# OpenRobot.net
KiCad netlist of a schematic drawn in EAGLE
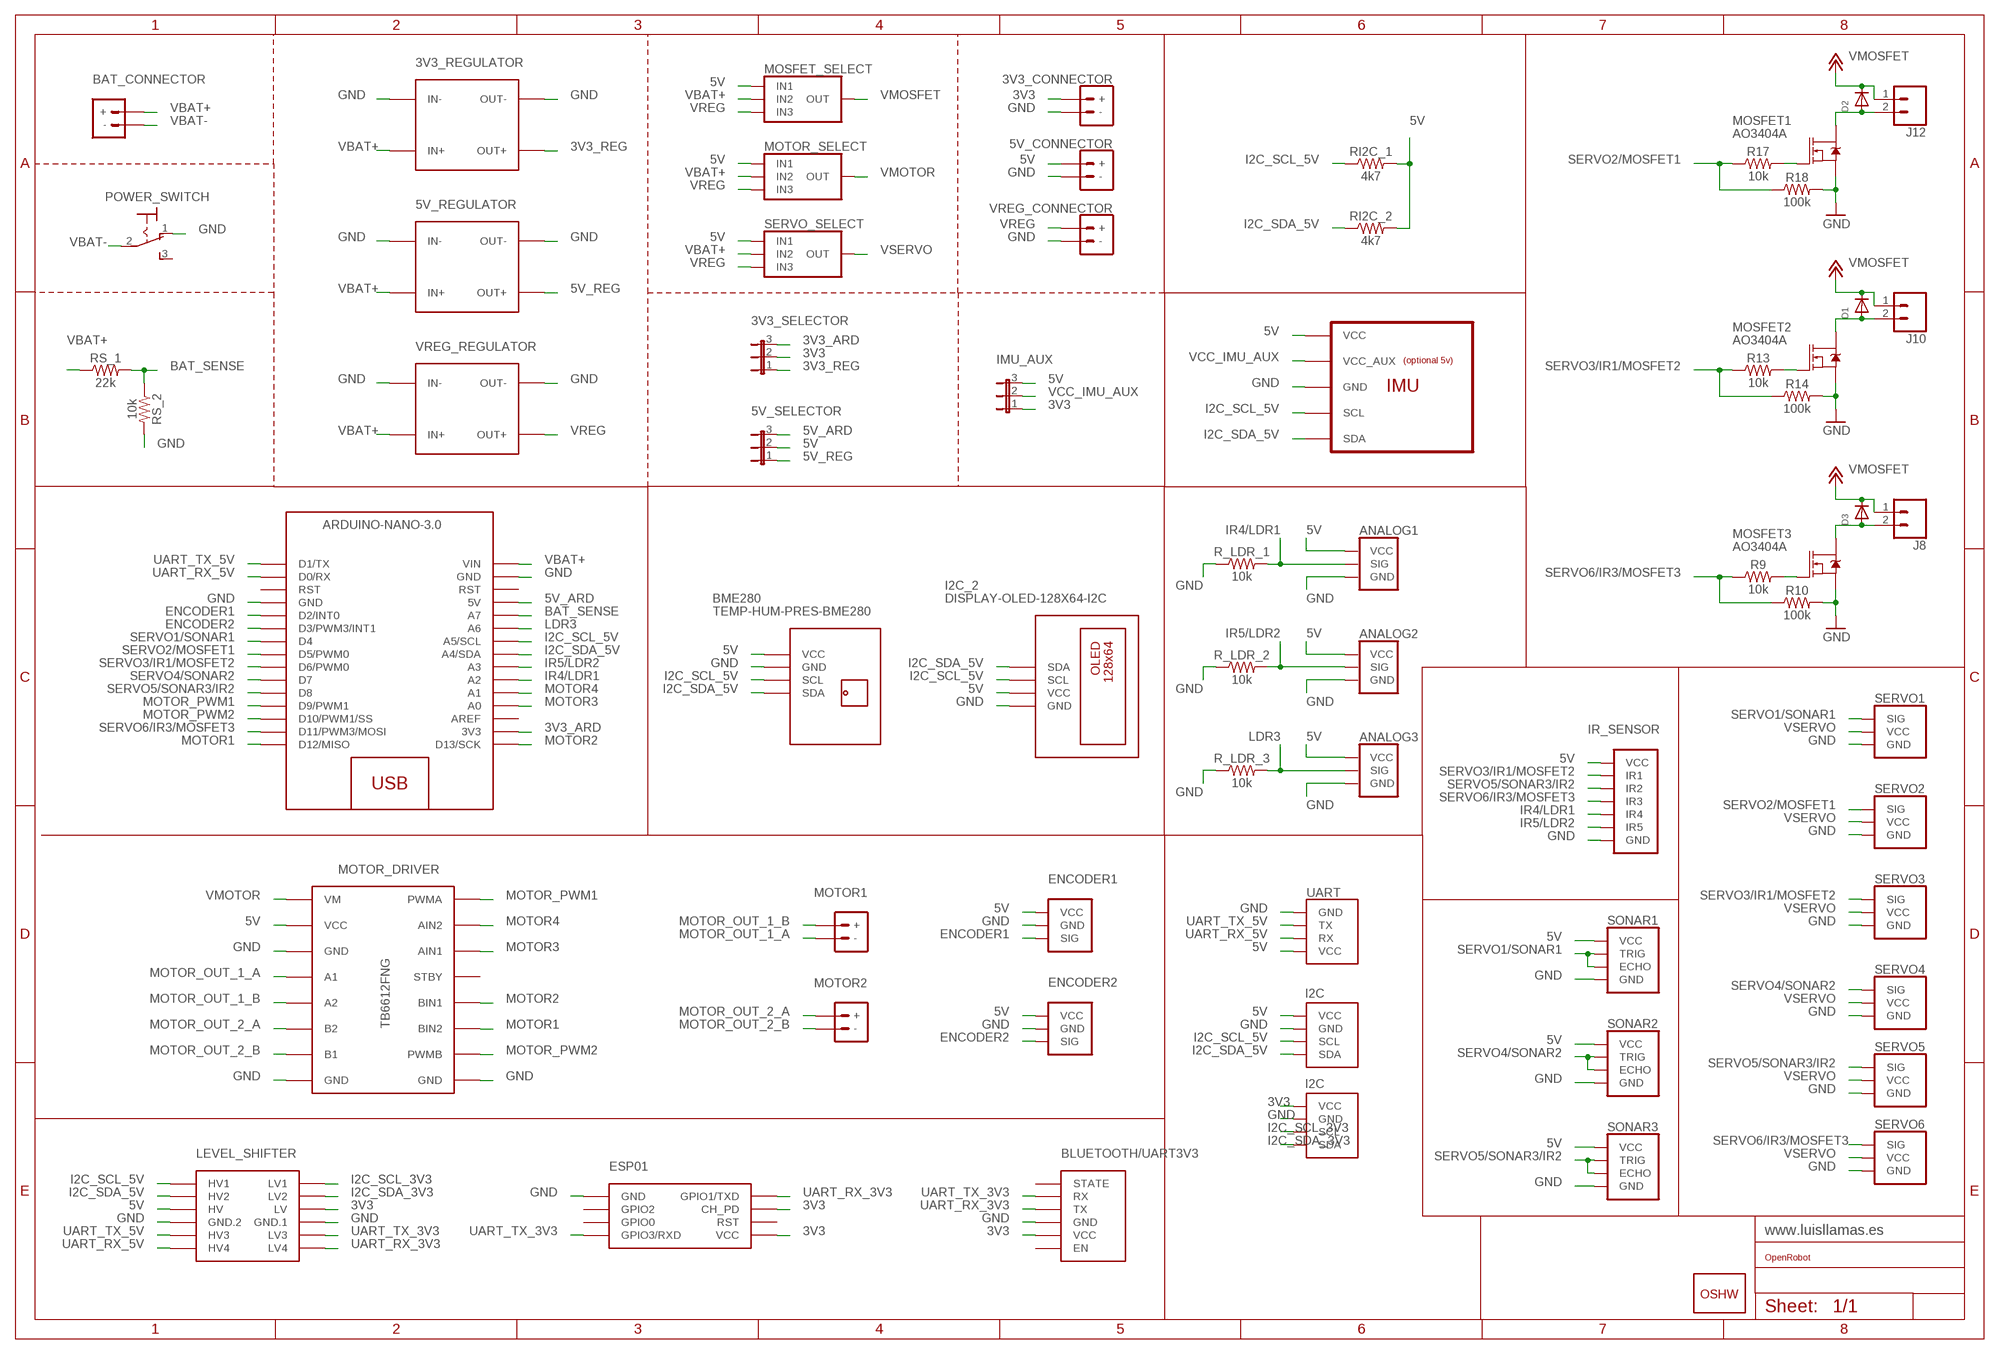
[diagram p0: schematic, sheet 1]

(export (version "E")
  (design (tool "Eeschema 10.0.6"))
  (components
    (comp (ref "3V3_CONNECTOR")
      (value "MOTOR-TERMINAL2.54MM_SCREWTERM")
      (footprint "eagle-import:1X02_2.54_SCREWTERM")
      (libsource (lib "eagle-import") (part "MOTOR-TERMINAL2.54MM_SCREWTERM"))
    )
    (comp (ref "3V3_REGULATOR")
      (value "MINI-DC-STEP-DOWN-MP2307")
      (footprint "eagle-import:MINI-DC-STEP-DOWN-MP2307")
      (libsource (lib "eagle-import") (part "MINI-DC-STEP-DOWN-MP2307"))
    )
    (comp (ref "3V3_SELECTOR")
      (value "1")
      (footprint "eagle-import:JP2")
      (libsource (lib "eagle-import") (part "JP2E"))
    )
    (comp (ref "5V_CONNECTOR")
      (value "MOTOR-TERMINAL2.54MM_SCREWTERM")
      (footprint "eagle-import:1X02_2.54_SCREWTERM")
      (libsource (lib "eagle-import") (part "MOTOR-TERMINAL2.54MM_SCREWTERM"))
    )
    (comp (ref "5V_REGULATOR")
      (value "MINI-DC-STEP-DOWN-MP2307")
      (footprint "eagle-import:MINI-DC-STEP-DOWN-MP2307")
      (libsource (lib "eagle-import") (part "MINI-DC-STEP-DOWN-MP2307"))
    )
    (comp (ref "5V_SELECTOR")
      (value "1")
      (footprint "eagle-import:JP2")
      (libsource (lib "eagle-import") (part "JP2E"))
    )
    (comp (ref "ANALOG1")
      (value "LDR/OCT")
      (footprint "eagle-import:LDR")
      (libsource (lib "eagle-import") (part "LDR/OCT"))
    )
    (comp (ref "ANALOG2")
      (value "LDR/OCT")
      (footprint "eagle-import:LDR")
      (libsource (lib "eagle-import") (part "LDR/OCT"))
    )
    (comp (ref "ANALOG3")
      (value "LDR/OCT")
      (footprint "eagle-import:LDR")
      (libsource (lib "eagle-import") (part "LDR/OCT"))
    )
    (comp (ref "ARDUINO_NANO1")
      (value "ARDUINO-NANO-3.0")
      (footprint "eagle-import:ARDUINO-NANO-3.0")
      (libsource (lib "eagle-import") (part "ARDUINO-NANO-3.0"))
    )
    (comp (ref "BAT_CONNECTOR")
      (value "POWER-TERMINAL5MM")
      (footprint "eagle-import:SCREWTERMINAL-5MM-2")
      (libsource (lib "eagle-import") (part "POWER-TERMINAL5MM"))
    )
    (comp (ref "BLUETOOTH/UART3V3")
      (value "BLUETOOTH-HC-05")
      (footprint "eagle-import:BLUETOOTH-HC-05")
      (libsource (lib "eagle-import") (part "BLUETOOTH-HC-05"))
    )
    (comp (ref "BME280")
      (value "TEMP-HUM-PRES-BME280")
      (footprint "eagle-import:TEMP-HUM-PRES-BME280")
      (libsource (lib "eagle-import") (part "TEMP-HUM-PRES-BME280"))
    )
    (comp (ref "D1")
      (value "DIODESOD-123")
      (footprint "eagle-import:SOD-123")
      (libsource (lib "eagle-import") (part "DIODESOD-123"))
    )
    (comp (ref "D2")
      (value "DIODESOD-123")
      (footprint "eagle-import:SOD-123")
      (libsource (lib "eagle-import") (part "DIODESOD-123"))
    )
    (comp (ref "D3")
      (value "DIODESOD-123")
      (footprint "eagle-import:SOD-123")
      (libsource (lib "eagle-import") (part "DIODESOD-123"))
    )
    (comp (ref "ENCODER1")
      (value "ENCODER/OCT")
      (footprint "eagle-import:ENCODER")
      (libsource (lib "eagle-import") (part "ENCODER/OCT"))
    )
    (comp (ref "ENCODER2")
      (value "ENCODER/OCT")
      (footprint "eagle-import:ENCODER")
      (libsource (lib "eagle-import") (part "ENCODER/OCT"))
    )
    (comp (ref "GOLD_ORB_SM1")
      (value "OSHWLOGO_GOLD_ORB_MED")
      (footprint "eagle-import:OSHW1")
      (libsource (lib "eagle-import") (part "OSHWLOGO_GOLD_ORB_MED"))
    )
    (comp (ref "I2C_1")
      (value "I2C")
      (footprint "eagle-import:I2C_VCC_GND_SCL_SDA")
      (libsource (lib "eagle-import") (part "GENERIC_I2CVCC_GND_SCL_SDA"))
    )
    (comp (ref "I2C_2")
      (value "DISPLAY-OLED-128X64-I2C")
      (footprint "eagle-import:DISPLAY-OLED-128X64-I2C")
      (libsource (lib "eagle-import") (part "DISPLAY-OLED-128X64-I2C"))
    )
    (comp (ref "I2C_3")
      (value "I2C")
      (footprint "eagle-import:I2C_VCC_GND_SCL_SDA")
      (libsource (lib "eagle-import") (part "GENERIC_I2CVCC_GND_SCL_SDA"))
    )
    (comp (ref "IMU_AUX")
      (value "1")
      (footprint "eagle-import:JP2")
      (libsource (lib "eagle-import") (part "JP2E"))
    )
    (comp (ref "IR_SENSOR")
      (value "IR-5/OCT")
      (footprint "eagle-import:IR-5")
      (libsource (lib "eagle-import") (part "IR-5/OCT"))
    )
    (comp (ref "J8")
      (value "CONN_02LOCK_LONGPADS")
      (footprint "eagle-import:1X02_LOCK_LONGPADS")
      (libsource (lib "eagle-import") (part "CONN_02LOCK_LONGPADS"))
    )
    (comp (ref "J10")
      (value "CONN_02LOCK_LONGPADS")
      (footprint "eagle-import:1X02_LOCK_LONGPADS")
      (libsource (lib "eagle-import") (part "CONN_02LOCK_LONGPADS"))
    )
    (comp (ref "J12")
      (value "CONN_02LOCK_LONGPADS")
      (footprint "eagle-import:1X02_LOCK_LONGPADS")
      (libsource (lib "eagle-import") (part "CONN_02LOCK_LONGPADS"))
    )
    (comp (ref "LEVEL_SHIFTER")
      (value "LEVEL-SHIFTER-4CH")
      (footprint "eagle-import:LEVEL-SHIFTER-4CH")
      (libsource (lib "eagle-import") (part "LEVEL-SHIFTER-4CH"))
    )
    (comp (ref "MOSFET1")
      (value "AO3404A")
      (footprint "eagle-import:SOT23-3")
      (libsource (lib "eagle-import") (part "MOSFET-NCH-AO3404A"))
    )
    (comp (ref "MOSFET2")
      (value "AO3404A")
      (footprint "eagle-import:SOT23-3")
      (libsource (lib "eagle-import") (part "MOSFET-NCH-AO3404A"))
    )
    (comp (ref "MOSFET3")
      (value "AO3404A")
      (footprint "eagle-import:SOT23-3")
      (libsource (lib "eagle-import") (part "MOSFET-NCH-AO3404A"))
    )
    (comp (ref "MOSFET_SELECT")
      (value "JUMPER_3-1")
      (footprint "eagle-import:JUMPER_3-1")
      (libsource (lib "eagle-import") (part "JUMPER_3-1"))
    )
    (comp (ref "MOTOR1")
      (value "MOTOR-TERMINAL5MM")
      (footprint "eagle-import:SCREWTERMINAL-5MM-2")
      (libsource (lib "eagle-import") (part "MOTOR-TERMINAL5MM"))
    )
    (comp (ref "MOTOR2")
      (value "MOTOR-TERMINAL5MM")
      (footprint "eagle-import:SCREWTERMINAL-5MM-2")
      (libsource (lib "eagle-import") (part "MOTOR-TERMINAL5MM"))
    )
    (comp (ref "MOTOR_DRIVER")
      (value "TB6612FNG")
      (footprint "eagle-import:TB6612FNG")
      (libsource (lib "eagle-import") (part "TB6612FNG"))
    )
    (comp (ref "MOTOR_SELECT")
      (value "JUMPER_3-1")
      (footprint "eagle-import:JUMPER_3-1")
      (libsource (lib "eagle-import") (part "JUMPER_3-1"))
    )
    (comp (ref "POWER_SWITCH")
      (value "LEVER-POWER-SWITCH")
      (footprint "eagle-import:M9040P")
      (libsource (lib "eagle-import") (part "LEVER-POWER-SWITCH"))
    )
    (comp (ref "R9")
      (value "10k")
      (footprint "eagle-import:1206")
      (libsource (lib "eagle-import") (part "RESISTOR1206"))
    )
    (comp (ref "R10")
      (value "100k")
      (footprint "eagle-import:1206")
      (libsource (lib "eagle-import") (part "RESISTOR1206"))
    )
    (comp (ref "R13")
      (value "10k")
      (footprint "eagle-import:1206")
      (libsource (lib "eagle-import") (part "RESISTOR1206"))
    )
    (comp (ref "R14")
      (value "100k")
      (footprint "eagle-import:1206")
      (libsource (lib "eagle-import") (part "RESISTOR1206"))
    )
    (comp (ref "R17")
      (value "10k")
      (footprint "eagle-import:1206")
      (libsource (lib "eagle-import") (part "RESISTOR1206"))
    )
    (comp (ref "R18")
      (value "100k")
      (footprint "eagle-import:1206")
      (libsource (lib "eagle-import") (part "RESISTOR1206"))
    )
    (comp (ref "RI2C_1")
      (value "4k7")
      (footprint "eagle-import:1206")
      (libsource (lib "eagle-import") (part "RESISTOR1206"))
    )
    (comp (ref "RI2C_2")
      (value "4k7")
      (footprint "eagle-import:1206")
      (libsource (lib "eagle-import") (part "RESISTOR1206"))
    )
    (comp (ref "RS_1")
      (value "22k")
      (footprint "eagle-import:1206")
      (libsource (lib "eagle-import") (part "RESISTOR1206"))
    )
    (comp (ref "RS_2")
      (value "10k")
      (footprint "eagle-import:1206")
      (libsource (lib "eagle-import") (part "RESISTOR1206"))
    )
    (comp (ref "R_LDR_1")
      (value "10k")
      (footprint "eagle-import:1206")
      (libsource (lib "eagle-import") (part "RESISTOR1206"))
    )
    (comp (ref "R_LDR_2")
      (value "10k")
      (footprint "eagle-import:1206")
      (libsource (lib "eagle-import") (part "RESISTOR1206"))
    )
    (comp (ref "R_LDR_3")
      (value "10k")
      (footprint "eagle-import:1206")
      (libsource (lib "eagle-import") (part "RESISTOR1206"))
    )
    (comp (ref "SERVO1")
      (value "SERVOSERVO")
      (footprint "eagle-import:SERVO")
      (libsource (lib "eagle-import") (part "SERVOSERVO"))
    )
    (comp (ref "SERVO2")
      (value "SERVOSERVO")
      (footprint "eagle-import:SERVO")
      (libsource (lib "eagle-import") (part "SERVOSERVO"))
    )
    (comp (ref "SERVO3")
      (value "SERVOSERVO")
      (footprint "eagle-import:SERVO")
      (libsource (lib "eagle-import") (part "SERVOSERVO"))
    )
    (comp (ref "SERVO4")
      (value "SERVOSERVO")
      (footprint "eagle-import:SERVO")
      (libsource (lib "eagle-import") (part "SERVOSERVO"))
    )
    (comp (ref "SERVO5")
      (value "SERVOSERVO")
      (footprint "eagle-import:SERVO")
      (libsource (lib "eagle-import") (part "SERVOSERVO"))
    )
    (comp (ref "SERVO6")
      (value "SERVOSERVO")
      (footprint "eagle-import:SERVO")
      (libsource (lib "eagle-import") (part "SERVOSERVO"))
    )
    (comp (ref "SERVO_SELECT")
      (value "JUMPER_3-1")
      (footprint "eagle-import:JUMPER_3-1")
      (libsource (lib "eagle-import") (part "JUMPER_3-1"))
    )
    (comp (ref "SONAR1")
      (value "ULTRASONIC/OCT")
      (footprint "eagle-import:ULTRASONIC")
      (libsource (lib "eagle-import") (part "ULTRASONIC/OCT"))
    )
    (comp (ref "SONAR2")
      (value "ULTRASONIC/OCT")
      (footprint "eagle-import:ULTRASONIC")
      (libsource (lib "eagle-import") (part "ULTRASONIC/OCT"))
    )
    (comp (ref "SONAR3")
      (value "ULTRASONIC/OCT")
      (footprint "eagle-import:ULTRASONIC")
      (libsource (lib "eagle-import") (part "ULTRASONIC/OCT"))
    )
    (comp (ref "U$1")
      (value "ESP01")
      (footprint "eagle-import:ESP01")
      (libsource (lib "eagle-import") (part "ESP01"))
    )
    (comp (ref "U1")
      (value "IMU_6/9/10DOFMPU6050")
      (footprint "eagle-import:IMU_6_9_10DOF")
      (libsource (lib "eagle-import") (part "IMU_6/9/10DOFMPU6050"))
    )
    (comp (ref "UART")
      (value "UART")
      (footprint "eagle-import:GENERIC_UART")
      (libsource (lib "eagle-import") (part "GENERIC_UARTGND_TX_RX_VCC"))
    )
    (comp (ref "VREG_CONNECTOR")
      (value "MOTOR-TERMINAL2.54MM_SCREWTERM")
      (footprint "eagle-import:1X02_2.54_SCREWTERM")
      (libsource (lib "eagle-import") (part "MOTOR-TERMINAL2.54MM_SCREWTERM"))
    )
    (comp (ref "VREG_REGULATOR")
      (value "MINI-DC-STEP-DOWN-MP2307")
      (footprint "eagle-import:MINI-DC-STEP-DOWN-MP2307")
      (libsource (lib "eagle-import") (part "MINI-DC-STEP-DOWN-MP2307"))
    )
  )
  (nets
    (net (code "1") (name "+12V") (class "Default")
      (node (ref "D1") (pin "C") (pinfunction "C_C") (pintype "passive"))
      (node (ref "D2") (pin "C") (pinfunction "C_C") (pintype "passive"))
      (node (ref "D3") (pin "C") (pinfunction "C_C") (pintype "passive"))
      (node (ref "J10") (pin "1") (pinfunction "1_1") (pintype "passive"))
      (node (ref "J12") (pin "1") (pinfunction "1_1") (pintype "passive"))
      (node (ref "J8") (pin "1") (pinfunction "1_1") (pintype "passive"))
      (node (ref "MOSFET_SELECT") (pin "OUT") (pinfunction "OUT_OUT") (pintype "passive"))
    )
    (net (code "2") (name "/3V3") (class "Default")
      (node (ref "3V3_CONNECTOR") (pin "+") (pinfunction "+_+") (pintype "passive"))
      (node (ref "3V3_SELECTOR") (pin "2") (pinfunction "2_2") (pintype "passive"))
      (node (ref "BLUETOOTH/UART3V3") (pin "VCC") (pinfunction "VCC_VCC") (pintype "power_in"))
      (node (ref "I2C_3") (pin "VCC") (pinfunction "VCC_VCC") (pintype "power_in"))
      (node (ref "IMU_AUX") (pin "1") (pinfunction "1_1") (pintype "passive"))
      (node (ref "LEVEL_SHIFTER") (pin "J1.3") (pinfunction "LV_J1.3") (pintype "power_in"))
      (node (ref "U$1") (pin "CH_PD") (pinfunction "CH_PD_CH_PD") (pintype "bidirectional"))
      (node (ref "U$1") (pin "VCC") (pinfunction "VCC_VCC") (pintype "power_in"))
    )
    (net (code "3") (name "/3V3_ARD") (class "Default")
      (node (ref "3V3_SELECTOR") (pin "3") (pinfunction "3_3") (pintype "passive"))
      (node (ref "ARDUINO_NANO1") (pin "3V3") (pinfunction "3V3_3V3") (pintype "power_in"))
    )
    (net (code "4") (name "/3V3_REG") (class "Default")
      (node (ref "3V3_REGULATOR") (pin "OUT+") (pinfunction "OUT+_OUT+") (pintype "bidirectional"))
      (node (ref "3V3_REGULATOR") (pin "OUT2.+") (pinfunction "OUT+_OUT2.+") (pintype "bidirectional"))
      (node (ref "3V3_SELECTOR") (pin "1") (pinfunction "1_1") (pintype "passive"))
    )
    (net (code "5") (name "/5V") (class "Default")
      (node (ref "5V_CONNECTOR") (pin "+") (pinfunction "+_+") (pintype "passive"))
      (node (ref "5V_SELECTOR") (pin "2") (pinfunction "2_2") (pintype "passive"))
      (node (ref "ANALOG1") (pin "VCC") (pinfunction "VCC_VCC") (pintype "power_in"))
      (node (ref "ANALOG2") (pin "VCC") (pinfunction "VCC_VCC") (pintype "power_in"))
      (node (ref "ANALOG3") (pin "VCC") (pinfunction "VCC_VCC") (pintype "power_in"))
      (node (ref "BME280") (pin "VCC") (pinfunction "VCC_VCC") (pintype "power_in"))
      (node (ref "ENCODER1") (pin "VCC") (pinfunction "VCC_VCC") (pintype "power_in"))
      (node (ref "ENCODER2") (pin "VCC") (pinfunction "VCC_VCC") (pintype "power_in"))
      (node (ref "I2C_1") (pin "VCC") (pinfunction "VCC_VCC") (pintype "power_in"))
      (node (ref "I2C_2") (pin "VCC") (pinfunction "VCC_VCC") (pintype "power_in"))
      (node (ref "IMU_AUX") (pin "3") (pinfunction "3_3") (pintype "passive"))
      (node (ref "IR_SENSOR") (pin "VCC") (pinfunction "VCC_VCC") (pintype "power_in"))
      (node (ref "LEVEL_SHIFTER") (pin "J2.3") (pinfunction "HV_J2.3") (pintype "power_in"))
      (node (ref "MOSFET_SELECT") (pin "IN1") (pinfunction "IN1_IN1") (pintype "passive"))
      (node (ref "MOTOR_DRIVER") (pin "VCC") (pinfunction "VCC_VCC") (pintype "power_in"))
      (node (ref "MOTOR_SELECT") (pin "IN1") (pinfunction "IN1_IN1") (pintype "passive"))
      (node (ref "RI2C_1") (pin "2") (pinfunction "2_2") (pintype "passive"))
      (node (ref "RI2C_2") (pin "2") (pinfunction "2_2") (pintype "passive"))
      (node (ref "SERVO_SELECT") (pin "IN1") (pinfunction "IN1_IN1") (pintype "passive"))
      (node (ref "SONAR1") (pin "VCC") (pinfunction "VCC_VCC") (pintype "power_in"))
      (node (ref "SONAR2") (pin "VCC") (pinfunction "VCC_VCC") (pintype "power_in"))
      (node (ref "SONAR3") (pin "VCC") (pinfunction "VCC_VCC") (pintype "power_in"))
      (node (ref "U1") (pin "VCC") (pinfunction "VCC_VCC") (pintype "power_in"))
      (node (ref "UART") (pin "VCC") (pinfunction "VCC_VCC") (pintype "bidirectional"))
    )
    (net (code "6") (name "/5V_ARD") (class "Default")
      (node (ref "5V_SELECTOR") (pin "3") (pinfunction "3_3") (pintype "passive"))
      (node (ref "ARDUINO_NANO1") (pin "5V") (pinfunction "5V_5V") (pintype "bidirectional"))
    )
    (net (code "7") (name "/5V_REG") (class "Default")
      (node (ref "5V_REGULATOR") (pin "OUT+") (pinfunction "OUT+_OUT+") (pintype "bidirectional"))
      (node (ref "5V_REGULATOR") (pin "OUT2.+") (pinfunction "OUT+_OUT2.+") (pintype "bidirectional"))
      (node (ref "5V_SELECTOR") (pin "1") (pinfunction "1_1") (pintype "passive"))
    )
    (net (code "8") (name "/BAT_SENSE") (class "Default")
      (node (ref "ARDUINO_NANO1") (pin "A7") (pinfunction "A7_A7") (pintype "bidirectional"))
      (node (ref "RS_1") (pin "2") (pinfunction "2_2") (pintype "passive"))
      (node (ref "RS_2") (pin "1") (pinfunction "1_1") (pintype "passive"))
    )
    (net (code "9") (name "/ENCODER1") (class "Default")
      (node (ref "ARDUINO_NANO1") (pin "D2") (pinfunction "D2/INT0_D2") (pintype "bidirectional"))
      (node (ref "ENCODER1") (pin "SIG") (pinfunction "SIG_SIG") (pintype "bidirectional"))
    )
    (net (code "10") (name "/ENCODER2") (class "Default")
      (node (ref "ARDUINO_NANO1") (pin "D3") (pinfunction "D3/PWM3/INT1_D3") (pintype "bidirectional"))
      (node (ref "ENCODER2") (pin "SIG") (pinfunction "SIG_SIG") (pintype "bidirectional"))
    )
    (net (code "11") (name "/I2C_SCL_3V3") (class "Default")
      (node (ref "I2C_3") (pin "SCL") (pinfunction "SCL_SCL") (pintype "bidirectional"))
      (node (ref "LEVEL_SHIFTER") (pin "J1.1") (pinfunction "LV1_J1.1") (pintype "bidirectional"))
    )
    (net (code "12") (name "/I2C_SCL_5V") (class "Default")
      (node (ref "ARDUINO_NANO1") (pin "A5") (pinfunction "A5/SCL_A5") (pintype "bidirectional"))
      (node (ref "BME280") (pin "SCL") (pinfunction "SCL_SCL") (pintype "bidirectional"))
      (node (ref "I2C_1") (pin "SCL") (pinfunction "SCL_SCL") (pintype "bidirectional"))
      (node (ref "I2C_2") (pin "SCL") (pinfunction "SCL_SCL") (pintype "bidirectional"))
      (node (ref "LEVEL_SHIFTER") (pin "J2.1") (pinfunction "HV1_J2.1") (pintype "bidirectional"))
      (node (ref "RI2C_1") (pin "1") (pinfunction "1_1") (pintype "passive"))
      (node (ref "U1") (pin "SCL") (pinfunction "SCL_SCL") (pintype "bidirectional"))
    )
    (net (code "13") (name "/I2C_SDA_3V3") (class "Default")
      (node (ref "I2C_3") (pin "SDA") (pinfunction "SDA_SDA") (pintype "bidirectional"))
      (node (ref "LEVEL_SHIFTER") (pin "J1.2") (pinfunction "LV2_J1.2") (pintype "bidirectional"))
    )
    (net (code "14") (name "/I2C_SDA_5V") (class "Default")
      (node (ref "ARDUINO_NANO1") (pin "A4") (pinfunction "A4/SDA_A4") (pintype "bidirectional"))
      (node (ref "BME280") (pin "SDA") (pinfunction "SDA_SDA") (pintype "bidirectional"))
      (node (ref "I2C_1") (pin "SDA") (pinfunction "SDA_SDA") (pintype "bidirectional"))
      (node (ref "I2C_2") (pin "SDA") (pinfunction "SDA_SDA") (pintype "bidirectional"))
      (node (ref "LEVEL_SHIFTER") (pin "J2.2") (pinfunction "HV2_J2.2") (pintype "bidirectional"))
      (node (ref "RI2C_2") (pin "1") (pinfunction "1_1") (pintype "passive"))
      (node (ref "U1") (pin "SDA") (pinfunction "SDA_SDA") (pintype "bidirectional"))
    )
    (net (code "15") (name "/IR4{slash}LDR1") (class "Default")
      (node (ref "ANALOG1") (pin "SIG") (pinfunction "SIG_SIG") (pintype "bidirectional"))
      (node (ref "ARDUINO_NANO1") (pin "A2") (pinfunction "A2_A2") (pintype "bidirectional"))
      (node (ref "IR_SENSOR") (pin "4") (pinfunction "IR4_4") (pintype "bidirectional"))
      (node (ref "R_LDR_1") (pin "2") (pinfunction "2_2") (pintype "passive"))
    )
    (net (code "16") (name "/IR5{slash}LDR2") (class "Default")
      (node (ref "ANALOG2") (pin "SIG") (pinfunction "SIG_SIG") (pintype "bidirectional"))
      (node (ref "ARDUINO_NANO1") (pin "A3") (pinfunction "A3_A3") (pintype "bidirectional"))
      (node (ref "IR_SENSOR") (pin "5") (pinfunction "IR5_5") (pintype "bidirectional"))
      (node (ref "R_LDR_2") (pin "2") (pinfunction "2_2") (pintype "passive"))
    )
    (net (code "17") (name "/LDR3") (class "Default")
      (node (ref "ANALOG3") (pin "SIG") (pinfunction "SIG_SIG") (pintype "bidirectional"))
      (node (ref "ARDUINO_NANO1") (pin "A6") (pinfunction "A6_A6") (pintype "bidirectional"))
      (node (ref "R_LDR_3") (pin "2") (pinfunction "2_2") (pintype "passive"))
    )
    (net (code "18") (name "/MOTOR1") (class "Default")
      (node (ref "ARDUINO_NANO1") (pin "D12") (pinfunction "D12/MISO_D12") (pintype "bidirectional"))
      (node (ref "MOTOR_DRIVER") (pin "BIN2") (pinfunction "BIN2_BIN2") (pintype "bidirectional"))
    )
    (net (code "19") (name "/MOTOR2") (class "Default")
      (node (ref "ARDUINO_NANO1") (pin "D13") (pinfunction "D13/SCK_D13") (pintype "bidirectional"))
      (node (ref "MOTOR_DRIVER") (pin "BIN1") (pinfunction "BIN1_BIN1") (pintype "bidirectional"))
    )
    (net (code "20") (name "/MOTOR3") (class "Default")
      (node (ref "ARDUINO_NANO1") (pin "A0") (pinfunction "A0_A0") (pintype "bidirectional"))
      (node (ref "MOTOR_DRIVER") (pin "AIN1") (pinfunction "AIN1_AIN1") (pintype "bidirectional"))
    )
    (net (code "21") (name "/MOTOR4") (class "Default")
      (node (ref "ARDUINO_NANO1") (pin "A1") (pinfunction "A1_A1") (pintype "bidirectional"))
      (node (ref "MOTOR_DRIVER") (pin "AIN2") (pinfunction "AIN2_AIN2") (pintype "bidirectional"))
    )
    (net (code "22") (name "/MOTOR_OUT_1_A") (class "Default")
      (node (ref "MOTOR1") (pin "-") (pinfunction "-_-") (pintype "passive"))
      (node (ref "MOTOR_DRIVER") (pin "A1") (pinfunction "A1_A1") (pintype "bidirectional"))
    )
    (net (code "23") (name "/MOTOR_OUT_1_B") (class "Default")
      (node (ref "MOTOR1") (pin "+") (pinfunction "+_+") (pintype "passive"))
      (node (ref "MOTOR_DRIVER") (pin "A2") (pinfunction "A2_A2") (pintype "bidirectional"))
    )
    (net (code "24") (name "/MOTOR_OUT_2_A") (class "Default")
      (node (ref "MOTOR2") (pin "+") (pinfunction "+_+") (pintype "passive"))
      (node (ref "MOTOR_DRIVER") (pin "B2") (pinfunction "B2_B2") (pintype "bidirectional"))
    )
    (net (code "25") (name "/MOTOR_OUT_2_B") (class "Default")
      (node (ref "MOTOR2") (pin "-") (pinfunction "-_-") (pintype "passive"))
      (node (ref "MOTOR_DRIVER") (pin "B1") (pinfunction "B1_B1") (pintype "bidirectional"))
    )
    (net (code "26") (name "/MOTOR_PWM1") (class "Default")
      (node (ref "ARDUINO_NANO1") (pin "D9") (pinfunction "D9/PWM1_D9") (pintype "bidirectional"))
      (node (ref "MOTOR_DRIVER") (pin "PWMA") (pinfunction "PWMA_PWMA") (pintype "bidirectional"))
    )
    (net (code "27") (name "/MOTOR_PWM2") (class "Default")
      (node (ref "ARDUINO_NANO1") (pin "D10") (pinfunction "D10/PWM1/SS_D10") (pintype "bidirectional"))
      (node (ref "MOTOR_DRIVER") (pin "PWMB") (pinfunction "PWMB_PWMB") (pintype "bidirectional"))
    )
    (net (code "28") (name "/SERVO1{slash}SONAR1") (class "Default")
      (node (ref "ARDUINO_NANO1") (pin "D4") (pinfunction "D4_D4") (pintype "bidirectional"))
      (node (ref "SERVO1") (pin "SIG") (pinfunction "SIG_SIG") (pintype "bidirectional"))
      (node (ref "SONAR1") (pin "ECHO") (pinfunction "ECHO_ECHO") (pintype "bidirectional"))
      (node (ref "SONAR1") (pin "TRIG") (pinfunction "TRIG_TRIG") (pintype "bidirectional"))
    )
    (net (code "29") (name "/SERVO2{slash}MOSFET1") (class "Default")
      (node (ref "ARDUINO_NANO1") (pin "D5") (pinfunction "D5/PWM0_D5") (pintype "bidirectional"))
      (node (ref "R17") (pin "1") (pinfunction "1_1") (pintype "passive"))
      (node (ref "R18") (pin "1") (pinfunction "1_1") (pintype "passive"))
      (node (ref "SERVO2") (pin "SIG") (pinfunction "SIG_SIG") (pintype "bidirectional"))
    )
    (net (code "30") (name "/SERVO3{slash}IR1{slash}MOSFET2") (class "Default")
      (node (ref "ARDUINO_NANO1") (pin "D6") (pinfunction "D6/PWM0_D6") (pintype "bidirectional"))
      (node (ref "IR_SENSOR") (pin "1") (pinfunction "IR1_1") (pintype "bidirectional"))
      (node (ref "R13") (pin "1") (pinfunction "1_1") (pintype "passive"))
      (node (ref "R14") (pin "1") (pinfunction "1_1") (pintype "passive"))
      (node (ref "SERVO3") (pin "SIG") (pinfunction "SIG_SIG") (pintype "bidirectional"))
    )
    (net (code "31") (name "/SERVO4{slash}SONAR2") (class "Default")
      (node (ref "ARDUINO_NANO1") (pin "D7") (pinfunction "D7_D7") (pintype "bidirectional"))
      (node (ref "SERVO4") (pin "SIG") (pinfunction "SIG_SIG") (pintype "bidirectional"))
      (node (ref "SONAR2") (pin "ECHO") (pinfunction "ECHO_ECHO") (pintype "bidirectional"))
      (node (ref "SONAR2") (pin "TRIG") (pinfunction "TRIG_TRIG") (pintype "bidirectional"))
    )
    (net (code "32") (name "/SERVO5{slash}SONAR3{slash}IR2") (class "Default")
      (node (ref "ARDUINO_NANO1") (pin "D8") (pinfunction "D8_D8") (pintype "bidirectional"))
      (node (ref "IR_SENSOR") (pin "2") (pinfunction "IR2_2") (pintype "bidirectional"))
      (node (ref "SERVO5") (pin "SIG") (pinfunction "SIG_SIG") (pintype "bidirectional"))
      (node (ref "SONAR3") (pin "ECHO") (pinfunction "ECHO_ECHO") (pintype "bidirectional"))
      (node (ref "SONAR3") (pin "TRIG") (pinfunction "TRIG_TRIG") (pintype "bidirectional"))
    )
    (net (code "33") (name "/SERVO6{slash}IR3{slash}MOSFET3") (class "Default")
      (node (ref "ARDUINO_NANO1") (pin "D11") (pinfunction "D11/PWM3/MOSI_D11") (pintype "bidirectional"))
      (node (ref "IR_SENSOR") (pin "3") (pinfunction "IR3_3") (pintype "bidirectional"))
      (node (ref "R10") (pin "1") (pinfunction "1_1") (pintype "passive"))
      (node (ref "R9") (pin "1") (pinfunction "1_1") (pintype "passive"))
      (node (ref "SERVO6") (pin "SIG") (pinfunction "SIG_SIG") (pintype "bidirectional"))
    )
    (net (code "34") (name "/UART_RX_3V3") (class "Default")
      (node (ref "BLUETOOTH/UART3V3") (pin "TX") (pinfunction "TX_TX") (pintype "bidirectional"))
      (node (ref "LEVEL_SHIFTER") (pin "J1.6") (pinfunction "LV4_J1.6") (pintype "bidirectional"))
      (node (ref "U$1") (pin "TX") (pinfunction "GPIO1/TXD_TX") (pintype "bidirectional"))
    )
    (net (code "35") (name "/UART_RX_5V") (class "Default")
      (node (ref "ARDUINO_NANO1") (pin "RX0") (pinfunction "D0/RX_RX0") (pintype "bidirectional"))
      (node (ref "LEVEL_SHIFTER") (pin "J2.6") (pinfunction "HV4_J2.6") (pintype "bidirectional"))
      (node (ref "UART") (pin "RX") (pinfunction "RX_RX") (pintype "bidirectional"))
    )
    (net (code "36") (name "/UART_TX_3V3") (class "Default")
      (node (ref "BLUETOOTH/UART3V3") (pin "RX") (pinfunction "RX_RX") (pintype "bidirectional"))
      (node (ref "LEVEL_SHIFTER") (pin "J1.5") (pinfunction "LV3_J1.5") (pintype "bidirectional"))
      (node (ref "U$1") (pin "RX") (pinfunction "GPIO3/RXD_RX") (pintype "bidirectional"))
    )
    (net (code "37") (name "/UART_TX_5V") (class "Default")
      (node (ref "ARDUINO_NANO1") (pin "TX1") (pinfunction "D1/TX_TX1") (pintype "bidirectional"))
      (node (ref "LEVEL_SHIFTER") (pin "J2.5") (pinfunction "HV3_J2.5") (pintype "bidirectional"))
      (node (ref "UART") (pin "TX") (pinfunction "TX_TX") (pintype "power_in"))
    )
    (net (code "38") (name "/VBAT+") (class "Default")
      (node (ref "3V3_REGULATOR") (pin "IN+") (pinfunction "IN+_IN+") (pintype "bidirectional"))
      (node (ref "3V3_REGULATOR") (pin "IN.2+") (pinfunction "IN+_IN.2+") (pintype "bidirectional"))
      (node (ref "5V_REGULATOR") (pin "IN+") (pinfunction "IN+_IN+") (pintype "bidirectional"))
      (node (ref "5V_REGULATOR") (pin "IN.2+") (pinfunction "IN+_IN.2+") (pintype "bidirectional"))
      (node (ref "ARDUINO_NANO1") (pin "VIN") (pinfunction "VIN_VIN") (pintype "power_in"))
      (node (ref "BAT_CONNECTOR") (pin "+") (pinfunction "+_+") (pintype "passive"))
      (node (ref "MOSFET_SELECT") (pin "IN2") (pinfunction "IN2_IN2") (pintype "passive"))
      (node (ref "MOTOR_SELECT") (pin "IN2") (pinfunction "IN2_IN2") (pintype "passive"))
      (node (ref "RS_1") (pin "1") (pinfunction "1_1") (pintype "passive"))
      (node (ref "SERVO_SELECT") (pin "IN2") (pinfunction "IN2_IN2") (pintype "passive"))
      (node (ref "VREG_REGULATOR") (pin "IN+") (pinfunction "IN+_IN+") (pintype "bidirectional"))
      (node (ref "VREG_REGULATOR") (pin "IN.2+") (pinfunction "IN+_IN.2+") (pintype "bidirectional"))
    )
    (net (code "39") (name "/VBAT-") (class "Default")
      (node (ref "BAT_CONNECTOR") (pin "-") (pinfunction "-_-") (pintype "passive"))
      (node (ref "POWER_SWITCH") (pin "2") (pinfunction "P_2") (pintype "passive"))
    )
    (net (code "40") (name "/VCC_IMU_AUX") (class "Default")
      (node (ref "IMU_AUX") (pin "2") (pinfunction "2_2") (pintype "passive"))
      (node (ref "U1") (pin "VCC_AUX") (pinfunction "VCC_AUX_VCC_AUX") (pintype "power_in"))
    )
    (net (code "41") (name "/VMOTOR") (class "Default")
      (node (ref "MOTOR_DRIVER") (pin "VM") (pinfunction "VM_VM") (pintype "power_in"))
      (node (ref "MOTOR_SELECT") (pin "OUT") (pinfunction "OUT_OUT") (pintype "passive"))
    )
    (net (code "42") (name "/VREG") (class "Default")
      (node (ref "MOSFET_SELECT") (pin "IN3") (pinfunction "IN3_IN3") (pintype "passive"))
      (node (ref "MOTOR_SELECT") (pin "IN3") (pinfunction "IN3_IN3") (pintype "passive"))
      (node (ref "SERVO_SELECT") (pin "IN3") (pinfunction "IN3_IN3") (pintype "passive"))
      (node (ref "VREG_CONNECTOR") (pin "+") (pinfunction "+_+") (pintype "passive"))
      (node (ref "VREG_REGULATOR") (pin "OUT+") (pinfunction "OUT+_OUT+") (pintype "bidirectional"))
      (node (ref "VREG_REGULATOR") (pin "OUT2.+") (pinfunction "OUT+_OUT2.+") (pintype "bidirectional"))
    )
    (net (code "43") (name "/VSERVO") (class "Default")
      (node (ref "SERVO1") (pin "VCC") (pinfunction "VCC_VCC") (pintype "power_in"))
      (node (ref "SERVO2") (pin "VCC") (pinfunction "VCC_VCC") (pintype "power_in"))
      (node (ref "SERVO3") (pin "VCC") (pinfunction "VCC_VCC") (pintype "power_in"))
      (node (ref "SERVO4") (pin "VCC") (pinfunction "VCC_VCC") (pintype "power_in"))
      (node (ref "SERVO5") (pin "VCC") (pinfunction "VCC_VCC") (pintype "power_in"))
      (node (ref "SERVO6") (pin "VCC") (pinfunction "VCC_VCC") (pintype "power_in"))
      (node (ref "SERVO_SELECT") (pin "OUT") (pinfunction "OUT_OUT") (pintype "passive"))
    )
    (net (code "44") (name "GND") (class "Default")
      (node (ref "3V3_CONNECTOR") (pin "-") (pinfunction "-_-") (pintype "passive"))
      (node (ref "3V3_REGULATOR") (pin "IN-") (pinfunction "IN-_IN-") (pintype "bidirectional"))
      (node (ref "3V3_REGULATOR") (pin "OUT-") (pinfunction "OUT-_OUT-") (pintype "bidirectional"))
      (node (ref "5V_CONNECTOR") (pin "-") (pinfunction "-_-") (pintype "passive"))
      (node (ref "5V_REGULATOR") (pin "IN-") (pinfunction "IN-_IN-") (pintype "bidirectional"))
      (node (ref "5V_REGULATOR") (pin "OUT-") (pinfunction "OUT-_OUT-") (pintype "bidirectional"))
      (node (ref "ANALOG1") (pin "GND") (pinfunction "GND_GND") (pintype "power_in"))
      (node (ref "ANALOG2") (pin "GND") (pinfunction "GND_GND") (pintype "power_in"))
      (node (ref "ANALOG3") (pin "GND") (pinfunction "GND_GND") (pintype "power_in"))
      (node (ref "ARDUINO_NANO1") (pin "GND@1") (pinfunction "GND_GND@1") (pintype "power_in"))
      (node (ref "ARDUINO_NANO1") (pin "GND@2") (pinfunction "GND_GND@2") (pintype "power_in"))
      (node (ref "BLUETOOTH/UART3V3") (pin "GND") (pinfunction "GND_GND") (pintype "power_in"))
      (node (ref "BME280") (pin "GND") (pinfunction "GND_GND") (pintype "power_in"))
      (node (ref "ENCODER1") (pin "GND") (pinfunction "GND_GND") (pintype "power_in"))
      (node (ref "ENCODER2") (pin "GND") (pinfunction "GND_GND") (pintype "power_in"))
      (node (ref "I2C_1") (pin "GND") (pinfunction "GND_GND") (pintype "power_in"))
      (node (ref "I2C_2") (pin "GND") (pinfunction "GND_GND") (pintype "power_in"))
      (node (ref "I2C_3") (pin "GND") (pinfunction "GND_GND") (pintype "power_in"))
      (node (ref "IR_SENSOR") (pin "GND") (pinfunction "GND_GND") (pintype "power_in"))
      (node (ref "LEVEL_SHIFTER") (pin "J1.4") (pinfunction "GND.1_J1.4") (pintype "power_in"))
      (node (ref "LEVEL_SHIFTER") (pin "J2.4") (pinfunction "GND.2_J2.4") (pintype "power_in"))
      (node (ref "MOSFET1") (pin "2") (pinfunction "S_2") (pintype "bidirectional"))
      (node (ref "MOSFET2") (pin "2") (pinfunction "S_2") (pintype "bidirectional"))
      (node (ref "MOSFET3") (pin "2") (pinfunction "S_2") (pintype "bidirectional"))
      (node (ref "MOTOR_DRIVER") (pin "GND1") (pinfunction "GND_GND1") (pintype "bidirectional"))
      (node (ref "MOTOR_DRIVER") (pin "GND2") (pinfunction "GND_GND2") (pintype "power_in"))
      (node (ref "MOTOR_DRIVER") (pin "GND3") (pinfunction "GND_GND3") (pintype "power_in"))
      (node (ref "POWER_SWITCH") (pin "1") (pinfunction "O_1") (pintype "passive"))
      (node (ref "R10") (pin "2") (pinfunction "2_2") (pintype "passive"))
      (node (ref "R14") (pin "2") (pinfunction "2_2") (pintype "passive"))
      (node (ref "R18") (pin "2") (pinfunction "2_2") (pintype "passive"))
      (node (ref "RS_2") (pin "2") (pinfunction "2_2") (pintype "passive"))
      (node (ref "R_LDR_1") (pin "1") (pinfunction "1_1") (pintype "passive"))
      (node (ref "R_LDR_2") (pin "1") (pinfunction "1_1") (pintype "passive"))
      (node (ref "R_LDR_3") (pin "1") (pinfunction "1_1") (pintype "passive"))
      (node (ref "SERVO1") (pin "GND") (pinfunction "GND_GND") (pintype "power_in"))
      (node (ref "SERVO2") (pin "GND") (pinfunction "GND_GND") (pintype "power_in"))
      (node (ref "SERVO3") (pin "GND") (pinfunction "GND_GND") (pintype "power_in"))
      (node (ref "SERVO4") (pin "GND") (pinfunction "GND_GND") (pintype "power_in"))
      (node (ref "SERVO5") (pin "GND") (pinfunction "GND_GND") (pintype "power_in"))
      (node (ref "SERVO6") (pin "GND") (pinfunction "GND_GND") (pintype "power_in"))
      (node (ref "SONAR1") (pin "GND") (pinfunction "GND_GND") (pintype "power_in"))
      (node (ref "SONAR2") (pin "GND") (pinfunction "GND_GND") (pintype "power_in"))
      (node (ref "SONAR3") (pin "GND") (pinfunction "GND_GND") (pintype "power_in"))
      (node (ref "U$1") (pin "GND") (pinfunction "GND_GND") (pintype "power_in"))
      (node (ref "U1") (pin "GND") (pinfunction "GND_GND") (pintype "power_in"))
      (node (ref "UART") (pin "GND") (pinfunction "GND_GND") (pintype "power_in"))
      (node (ref "VREG_CONNECTOR") (pin "-") (pinfunction "-_-") (pintype "passive"))
      (node (ref "VREG_REGULATOR") (pin "IN-") (pinfunction "IN-_IN-") (pintype "bidirectional"))
      (node (ref "VREG_REGULATOR") (pin "OUT-") (pinfunction "OUT-_OUT-") (pintype "bidirectional"))
    )
    (net (code "45") (name "Net-(MOSFET1-D)") (class "Default")
      (node (ref "D2") (pin "A") (pinfunction "A_A") (pintype "passive"))
      (node (ref "J12") (pin "2") (pinfunction "2_2") (pintype "passive"))
      (node (ref "MOSFET1") (pin "3") (pinfunction "D_3") (pintype "bidirectional"))
    )
    (net (code "46") (name "Net-(MOSFET1-G)") (class "Default")
      (node (ref "MOSFET1") (pin "1") (pinfunction "G_1") (pintype "bidirectional"))
      (node (ref "R17") (pin "2") (pinfunction "2_2") (pintype "passive"))
    )
    (net (code "47") (name "Net-(MOSFET2-D)") (class "Default")
      (node (ref "D1") (pin "A") (pinfunction "A_A") (pintype "passive"))
      (node (ref "J10") (pin "2") (pinfunction "2_2") (pintype "passive"))
      (node (ref "MOSFET2") (pin "3") (pinfunction "D_3") (pintype "bidirectional"))
    )
    (net (code "48") (name "Net-(MOSFET2-G)") (class "Default")
      (node (ref "MOSFET2") (pin "1") (pinfunction "G_1") (pintype "bidirectional"))
      (node (ref "R13") (pin "2") (pinfunction "2_2") (pintype "passive"))
    )
    (net (code "49") (name "Net-(MOSFET3-D)") (class "Default")
      (node (ref "D3") (pin "A") (pinfunction "A_A") (pintype "passive"))
      (node (ref "J8") (pin "2") (pinfunction "2_2") (pintype "passive"))
      (node (ref "MOSFET3") (pin "3") (pinfunction "D_3") (pintype "bidirectional"))
    )
    (net (code "50") (name "Net-(MOSFET3-G)") (class "Default")
      (node (ref "MOSFET3") (pin "1") (pinfunction "G_1") (pintype "bidirectional"))
      (node (ref "R9") (pin "2") (pinfunction "2_2") (pintype "passive"))
    )
    (net (code "51") (name "unconnected-(ARDUINO_NANO1-AREF-PadREG)") (class "Default")
      (node (ref "ARDUINO_NANO1") (pin "REG") (pinfunction "AREF_REG") (pintype "bidirectional"))
    )
    (net (code "52") (name "unconnected-(ARDUINO_NANO1-RST-PadRST@1)") (class "Default")
      (node (ref "ARDUINO_NANO1") (pin "RST@1") (pinfunction "RST_RST@1") (pintype "bidirectional"))
    )
    (net (code "53") (name "unconnected-(ARDUINO_NANO1-RST-PadRST@2)") (class "Default")
      (node (ref "ARDUINO_NANO1") (pin "RST@2") (pinfunction "RST_RST@2") (pintype "bidirectional"))
    )
    (net (code "54") (name "unconnected-(BLUETOOTH/UART3V3-PadEN)") (class "Default")
      (node (ref "BLUETOOTH/UART3V3") (pin "EN") (pinfunction "EN_EN") (pintype "bidirectional"))
    )
    (net (code "55") (name "unconnected-(BLUETOOTH/UART3V3-PadSTATE)") (class "Default")
      (node (ref "BLUETOOTH/UART3V3") (pin "STATE") (pinfunction "STATE_STATE") (pintype "bidirectional"))
    )
    (net (code "56") (name "unconnected-(MOTOR_DRIVER-PadSTBY)") (class "Default")
      (node (ref "MOTOR_DRIVER") (pin "STBY") (pinfunction "STBY_STBY") (pintype "bidirectional"))
    )
    (net (code "57") (name "unconnected-(POWER_SWITCH-S-Pad3)") (class "Default")
      (node (ref "POWER_SWITCH") (pin "3") (pinfunction "S_3") (pintype "passive"))
    )
    (net (code "58") (name "unconnected-(U$1-PadGPIO0)") (class "Default")
      (node (ref "U$1") (pin "GPIO0") (pinfunction "GPIO0_GPIO0") (pintype "bidirectional"))
    )
    (net (code "59") (name "unconnected-(U$1-PadGPIO2)") (class "Default")
      (node (ref "U$1") (pin "GPIO2") (pinfunction "GPIO2_GPIO2") (pintype "bidirectional"))
    )
    (net (code "60") (name "unconnected-(U$1-PadRST)") (class "Default")
      (node (ref "U$1") (pin "RST") (pinfunction "RST_RST") (pintype "bidirectional"))
    )
  )
)
